# ATiny2PiRM12B.net
KiCad netlist of a schematic drawn in EAGLE
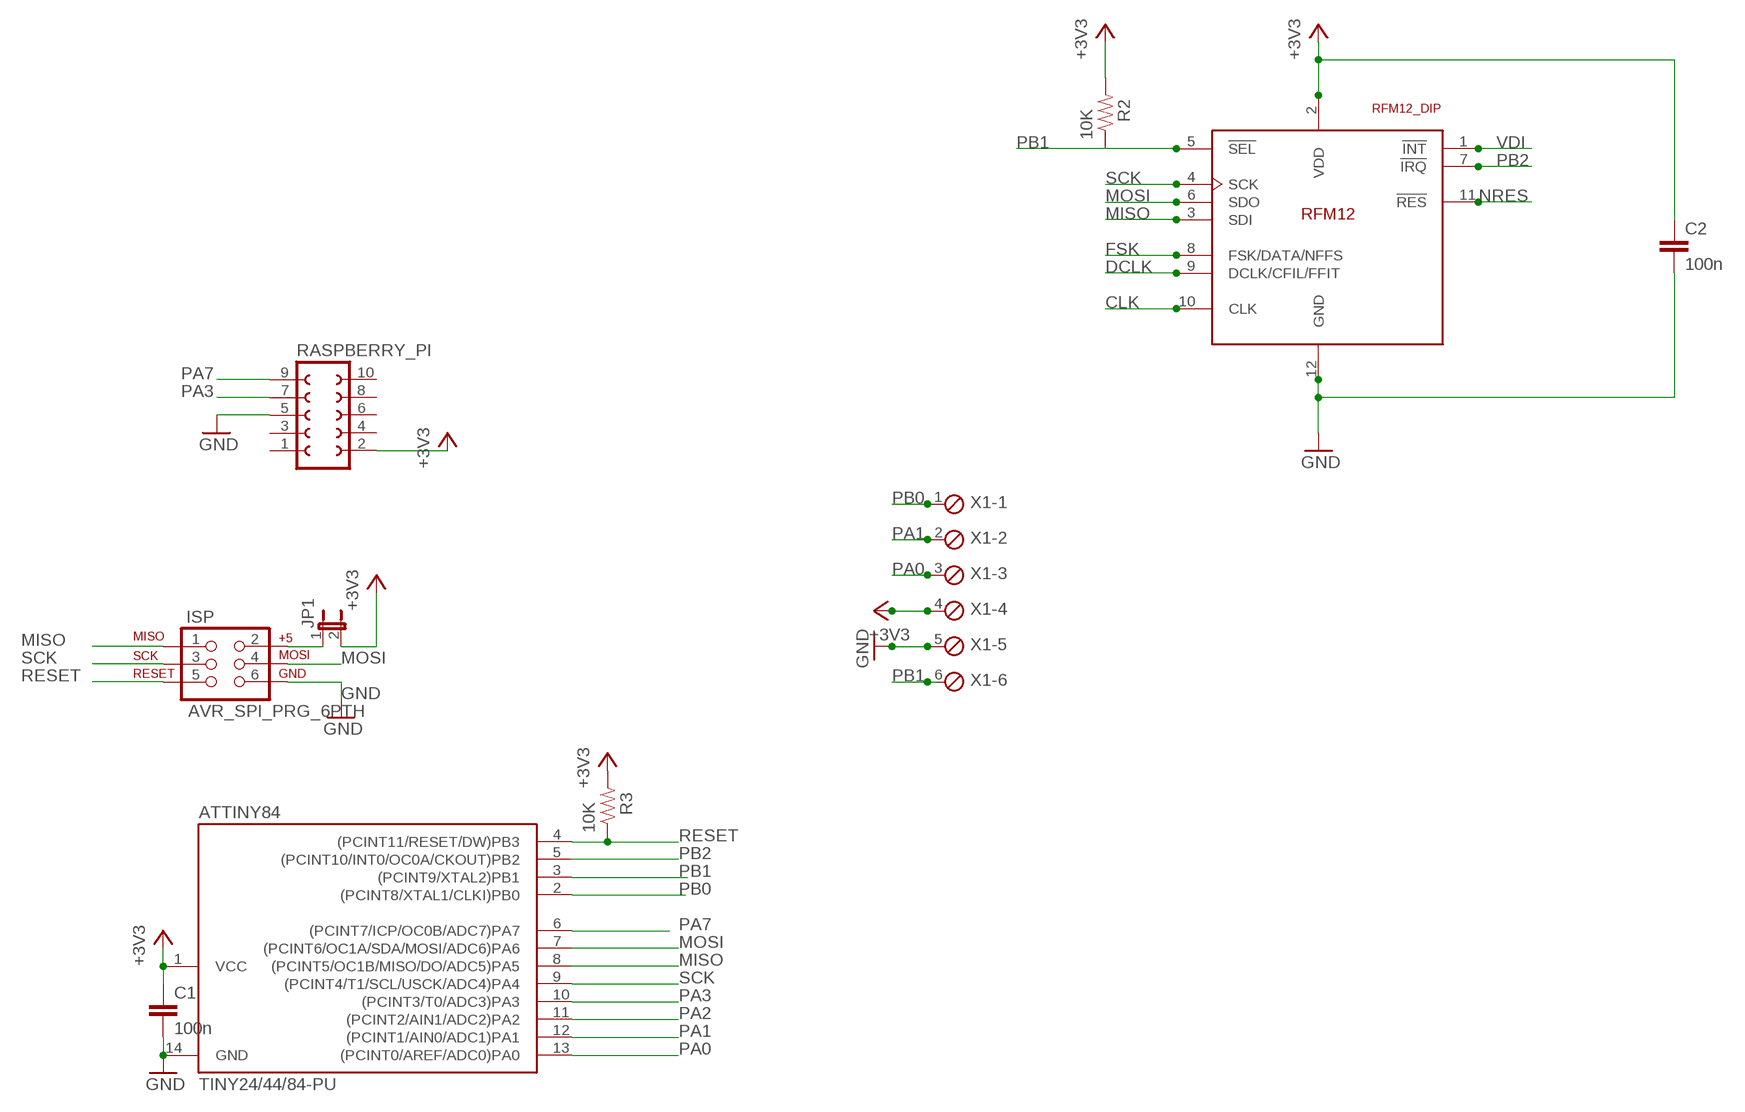
[diagram p0: schematic, sheet 1]

(export (version "E")
  (design (tool "Eeschema 10.0.6"))
  (components
    (comp (ref "ATTINY84")
      (value "TINY24/44/84-PU")
      (footprint "eagle-import:DIL14")
      (libsource (lib "eagle-import") (part "TINY24/44/84-PU"))
    )
    (comp (ref "C1")
      (value "100n")
      (footprint "eagle-import:C025-024X044")
      (libsource (lib "eagle-import") (part "C-EU025-024X044"))
    )
    (comp (ref "C2")
      (value "100n")
      (footprint "eagle-import:C025-024X044")
      (libsource (lib "eagle-import") (part "C-EU025-024X044"))
    )
    (comp (ref "ISP")
      (value "AVR_SPI_PRG_6PTH")
      (footprint "eagle-import:2X3")
      (libsource (lib "eagle-import") (part "AVR_SPI_PRG_6PTH"))
    )
    (comp (ref "JP1")
      (value "JUMPER-2PTH")
      (footprint "eagle-import:1X02")
      (libsource (lib "eagle-import") (part "JUMPER-2PTH"))
    )
    (comp (ref "R2")
      (value "10K")
      (footprint "eagle-import:AXIAL-0.3")
      (libsource (lib "eagle-import") (part "RESISTORAXIAL-0.3"))
    )
    (comp (ref "R3")
      (value "10K")
      (footprint "eagle-import:AXIAL-0.3")
      (libsource (lib "eagle-import") (part "RESISTORAXIAL-0.3"))
    )
    (comp (ref "RASPBERRY_PI")
      (value "FE05-2")
      (footprint "eagle-import:FE05-2")
      (libsource (lib "eagle-import") (part "FE05-2"))
    )
    (comp (ref "U$1")
      (value "RFM12_DIP")
      (footprint "eagle-import:DIL-2MM-2X06")
      (libsource (lib "eagle-import") (part "RFM12_DIP"))
    )
    (comp (ref "X1")
      (value "MPT6")
      (footprint "eagle-import:6POL254")
      (libsource (lib "eagle-import") (part "MPT6"))
    )
  )
  (nets
    (net (code "1") (name "+3V3") (class "Default")
      (node (ref "ATTINY84") (pin "1") (pinfunction "VCC_1") (pintype "power_in"))
      (node (ref "C1") (pin "1") (pinfunction "1_1") (pintype "passive"))
      (node (ref "C2") (pin "1") (pinfunction "1_1") (pintype "passive"))
      (node (ref "JP1") (pin "2") (pinfunction "2_2") (pintype "passive"))
      (node (ref "R2") (pin "P$2") (pinfunction "2_P$2") (pintype "passive"))
      (node (ref "R3") (pin "P$2") (pinfunction "2_P$2") (pintype "passive"))
      (node (ref "RASPBERRY_PI") (pin "2") (pinfunction "2_2") (pintype "passive"))
      (node (ref "U$1") (pin "2") (pinfunction "VDD_2") (pintype "power_in"))
      (node (ref "X1") (pin "4") (pinfunction "1_4") (pintype "passive"))
    )
    (net (code "2") (name "/CLK") (class "Default")
      (node (ref "U$1") (pin "10") (pinfunction "CLK_10") (pintype "output"))
    )
    (net (code "3") (name "/DCLK") (class "Default")
      (node (ref "U$1") (pin "9") (pinfunction "DCLK/CFIL/FFIT_9") (pintype "bidirectional"))
    )
    (net (code "4") (name "/FSK") (class "Default")
      (node (ref "U$1") (pin "8") (pinfunction "FSK/DATA/NFFS_8") (pintype "bidirectional"))
    )
    (net (code "5") (name "/MISO") (class "Default")
      (node (ref "ATTINY84") (pin "8") (pinfunction "(PCINT5/OC1B/MISO/DO/ADC5)PA5_8") (pintype "bidirectional"))
      (node (ref "ISP") (pin "1") (pinfunction "1_1") (pintype "passive"))
      (node (ref "U$1") (pin "3") (pinfunction "SDI_3") (pintype "input"))
    )
    (net (code "6") (name "/MOSI") (class "Default")
      (node (ref "ATTINY84") (pin "7") (pinfunction "(PCINT6/OC1A/SDA/MOSI/ADC6)PA6_7") (pintype "bidirectional"))
      (node (ref "ISP") (pin "4") (pinfunction "4_4") (pintype "passive"))
      (node (ref "U$1") (pin "6") (pinfunction "SDO_6") (pintype "output"))
    )
    (net (code "7") (name "/NRES") (class "Default")
      (node (ref "U$1") (pin "11") (pinfunction "~{RES}_11") (pintype "bidirectional"))
    )
    (net (code "8") (name "/PA0") (class "Default")
      (node (ref "ATTINY84") (pin "13") (pinfunction "(PCINT0/AREF/ADC0)PA0_13") (pintype "bidirectional"))
      (node (ref "X1") (pin "3") (pinfunction "1_3") (pintype "passive"))
    )
    (net (code "9") (name "/PA1") (class "Default")
      (node (ref "ATTINY84") (pin "12") (pinfunction "(PCINT1/AIN0/ADC1)PA1_12") (pintype "bidirectional"))
      (node (ref "X1") (pin "2") (pinfunction "1_2") (pintype "passive"))
    )
    (net (code "10") (name "/PA2") (class "Default")
      (node (ref "ATTINY84") (pin "11") (pinfunction "(PCINT2/AIN1/ADC2)PA2_11") (pintype "bidirectional"))
    )
    (net (code "11") (name "/PA3") (class "Default")
      (node (ref "ATTINY84") (pin "10") (pinfunction "(PCINT3/T0/ADC3)PA3_10") (pintype "bidirectional"))
      (node (ref "RASPBERRY_PI") (pin "7") (pinfunction "7_7") (pintype "passive"))
    )
    (net (code "12") (name "/PA7") (class "Default")
      (node (ref "ATTINY84") (pin "6") (pinfunction "(PCINT7/ICP/OC0B/ADC7)PA7_6") (pintype "bidirectional"))
      (node (ref "RASPBERRY_PI") (pin "9") (pinfunction "9_9") (pintype "passive"))
    )
    (net (code "13") (name "/PB0") (class "Default")
      (node (ref "ATTINY84") (pin "2") (pinfunction "(PCINT8/XTAL1/CLKI)PB0_2") (pintype "bidirectional"))
      (node (ref "X1") (pin "1") (pinfunction "1_1") (pintype "passive"))
    )
    (net (code "14") (name "/PB1") (class "Default")
      (node (ref "ATTINY84") (pin "3") (pinfunction "(PCINT9/XTAL2)PB1_3") (pintype "bidirectional"))
      (node (ref "R2") (pin "P$1") (pinfunction "1_P$1") (pintype "passive"))
      (node (ref "U$1") (pin "5") (pinfunction "~{SEL}_5") (pintype "input"))
      (node (ref "X1") (pin "6") (pinfunction "1_6") (pintype "passive"))
    )
    (net (code "15") (name "/PB2") (class "Default")
      (node (ref "ATTINY84") (pin "5") (pinfunction "(PCINT10/INT0/OC0A/CKOUT)PB2_5") (pintype "bidirectional"))
      (node (ref "U$1") (pin "7") (pinfunction "~{IRQ}_7") (pintype "output"))
    )
    (net (code "16") (name "/RESET") (class "Default")
      (node (ref "ATTINY84") (pin "4") (pinfunction "(PCINT11/RESET/DW)PB3_4") (pintype "bidirectional"))
      (node (ref "ISP") (pin "5") (pinfunction "5_5") (pintype "passive"))
      (node (ref "R3") (pin "P$1") (pinfunction "1_P$1") (pintype "passive"))
    )
    (net (code "17") (name "/SCK") (class "Default")
      (node (ref "ATTINY84") (pin "9") (pinfunction "(PCINT4/T1/SCL/USCK/ADC4)PA4_9") (pintype "bidirectional"))
      (node (ref "ISP") (pin "3") (pinfunction "3_3") (pintype "passive"))
      (node (ref "U$1") (pin "4") (pinfunction "SCK_4") (pintype "input"))
    )
    (net (code "18") (name "/VDI") (class "Default")
      (node (ref "U$1") (pin "1") (pinfunction "~{INT}_1") (pintype "bidirectional"))
    )
    (net (code "19") (name "GND") (class "Default")
      (node (ref "ATTINY84") (pin "14") (pinfunction "GND_14") (pintype "power_in"))
      (node (ref "C1") (pin "2") (pinfunction "2_2") (pintype "passive"))
      (node (ref "C2") (pin "2") (pinfunction "2_2") (pintype "passive"))
      (node (ref "ISP") (pin "6") (pinfunction "6_6") (pintype "passive"))
      (node (ref "RASPBERRY_PI") (pin "5") (pinfunction "5_5") (pintype "passive"))
      (node (ref "U$1") (pin "12") (pinfunction "GND_12") (pintype "passive"))
      (node (ref "X1") (pin "5") (pinfunction "1_5") (pintype "passive"))
    )
    (net (code "20") (name "Net-(ISP-Pad2)") (class "Default")
      (node (ref "ISP") (pin "2") (pinfunction "2_2") (pintype "passive"))
      (node (ref "JP1") (pin "1") (pinfunction "1_1") (pintype "passive"))
    )
    (net (code "21") (name "unconnected-(RASPBERRY_PI-Pad1)") (class "Default")
      (node (ref "RASPBERRY_PI") (pin "1") (pinfunction "1_1") (pintype "passive"))
    )
    (net (code "22") (name "unconnected-(RASPBERRY_PI-Pad3)") (class "Default")
      (node (ref "RASPBERRY_PI") (pin "3") (pinfunction "3_3") (pintype "passive"))
    )
    (net (code "23") (name "unconnected-(RASPBERRY_PI-Pad4)") (class "Default")
      (node (ref "RASPBERRY_PI") (pin "4") (pinfunction "4_4") (pintype "passive"))
    )
    (net (code "24") (name "unconnected-(RASPBERRY_PI-Pad6)") (class "Default")
      (node (ref "RASPBERRY_PI") (pin "6") (pinfunction "6_6") (pintype "passive"))
    )
    (net (code "25") (name "unconnected-(RASPBERRY_PI-Pad8)") (class "Default")
      (node (ref "RASPBERRY_PI") (pin "8") (pinfunction "8_8") (pintype "passive"))
    )
    (net (code "26") (name "unconnected-(RASPBERRY_PI-Pad10)") (class "Default")
      (node (ref "RASPBERRY_PI") (pin "10") (pinfunction "10_10") (pintype "passive"))
    )
  )
)
